# Adafruit_Infrared_IR_Remote_Receiver.net
KiCad netlist of a schematic drawn in EAGLE
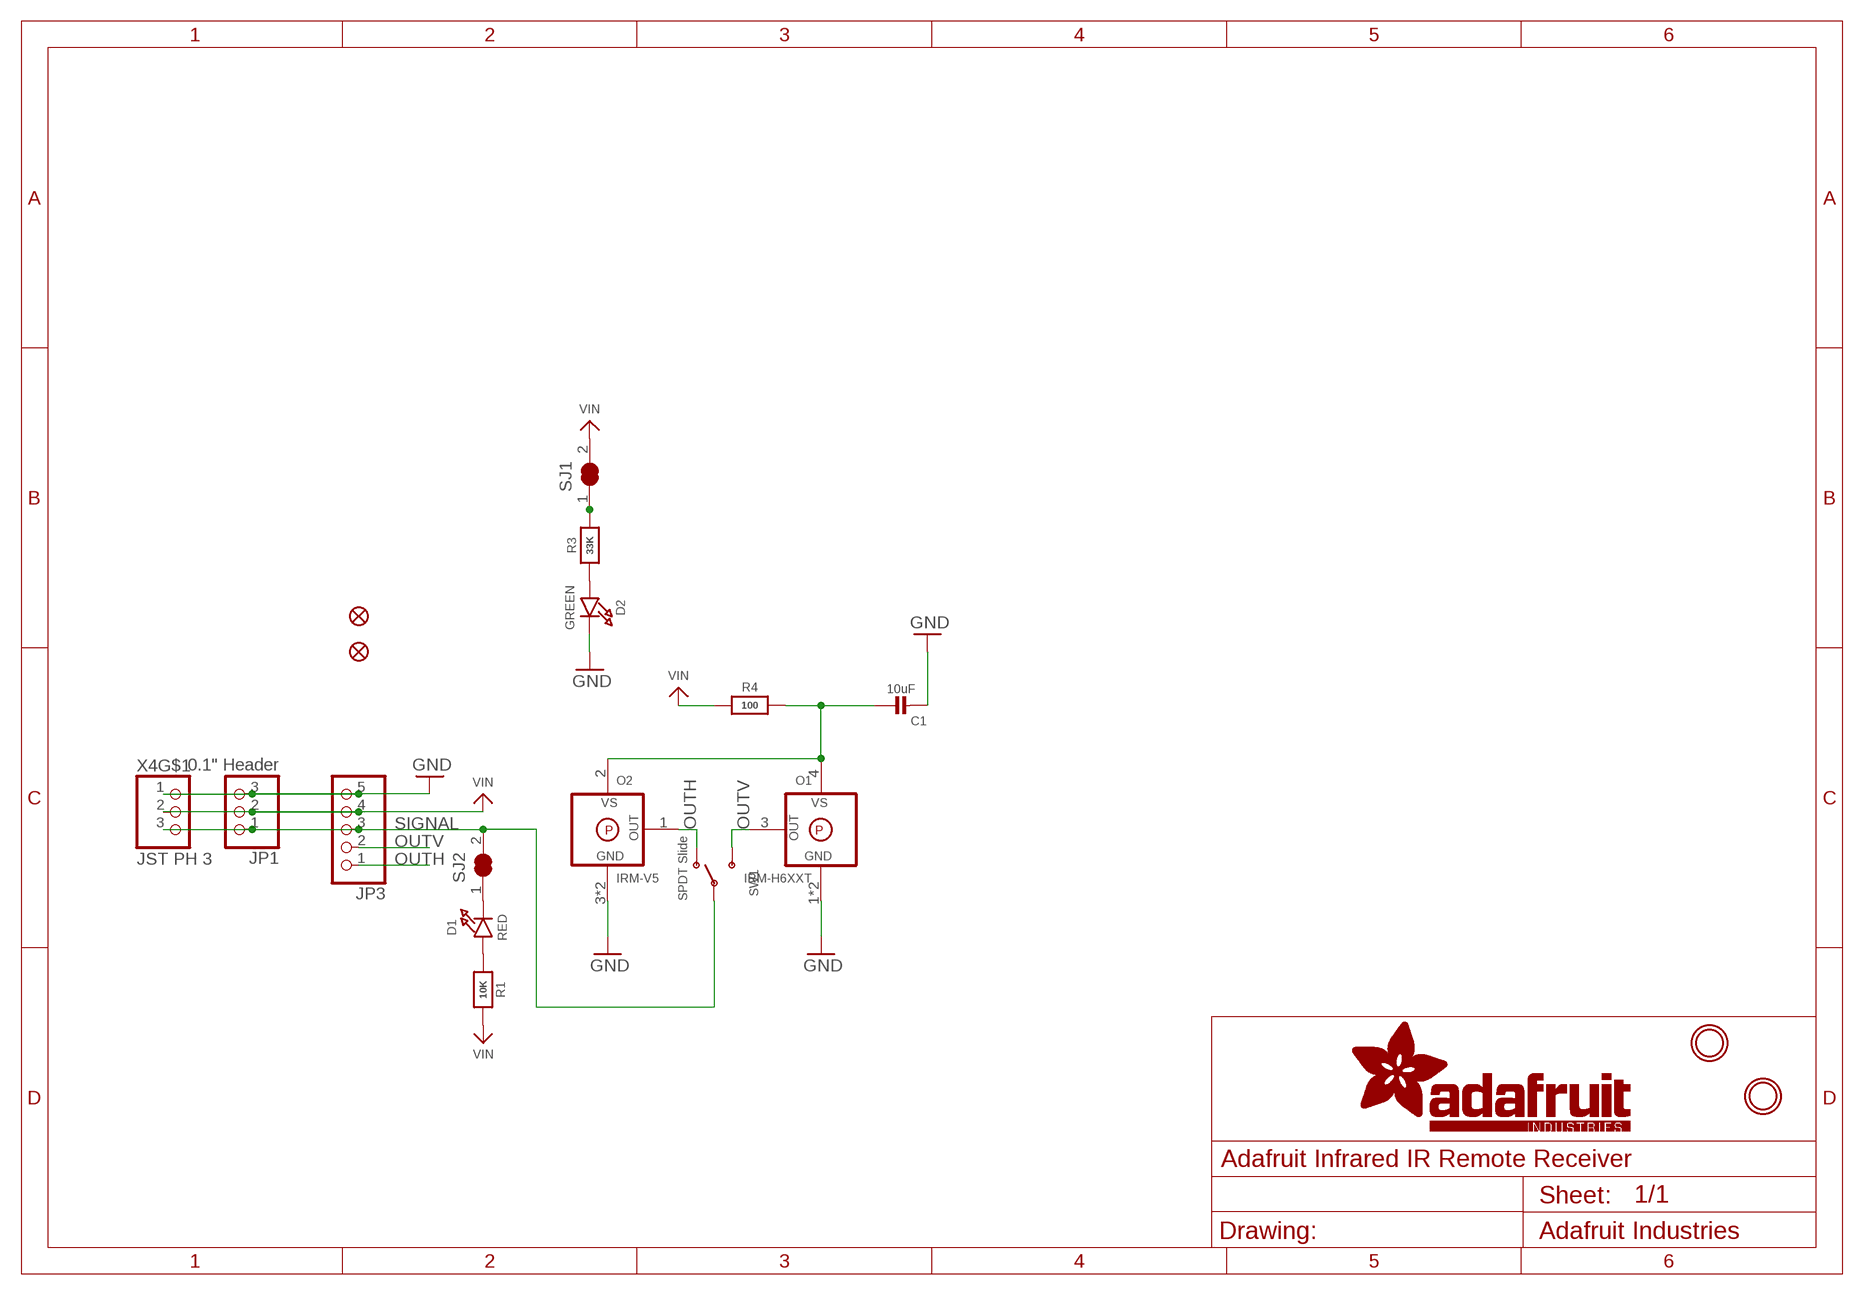
[diagram p0: schematic, sheet 1]

(export (version "E")
  (design (tool "Eeschema 10.0.6"))
  (components
    (comp (ref "C1")
      (value "10uF")
      (footprint "eagle-import:0805-NO")
      (libsource (lib "eagle-import") (part "CAP_CERAMIC0805-NOOUTLINE"))
    )
    (comp (ref "D1")
      (value "RED")
      (footprint "eagle-import:CHIPLED_0603_NOOUTLINE")
      (libsource (lib "eagle-import") (part "LED0603_NOOUTLINE"))
    )
    (comp (ref "D2")
      (value "GREEN")
      (footprint "eagle-import:CHIPLED_0603_NOOUTLINE")
      (libsource (lib "eagle-import") (part "LED0603_NOOUTLINE"))
    )
    (comp (ref "FID2")
      (value "FIDUCIAL_1MM")
      (footprint "eagle-import:FIDUCIAL_1MM")
      (libsource (lib "eagle-import") (part "FIDUCIAL_1MM"))
    )
    (comp (ref "FID3")
      (value "FIDUCIAL_1MM")
      (footprint "eagle-import:FIDUCIAL_1MM")
      (libsource (lib "eagle-import") (part "FIDUCIAL_1MM"))
    )
    (comp (ref "JP1")
      (value "0.1\" Header")
      (footprint "eagle-import:1X03_OVAL")
      (libsource (lib "eagle-import") (part "HEADER-1X3"))
    )
    (comp (ref "JP3")
      (value "HEADER-1X570MIL")
      (footprint "eagle-import:1X05_ROUND_70")
      (libsource (lib "eagle-import") (part "HEADER-1X570MIL"))
    )
    (comp (ref "O1")
      (value "IRM-H6XXT")
      (footprint "eagle-import:IRM-H6XXT")
      (libsource (lib "eagle-import") (part "GENERIC_IR_RECV_IRM-H6XXT"))
    )
    (comp (ref "O2")
      (value "IRM-V5")
      (footprint "eagle-import:IRM-V5")
      (libsource (lib "eagle-import") (part "GENERIC_IR_RECV_IRM-V5"))
    )
    (comp (ref "R1")
      (value "10K")
      (footprint "eagle-import:0603-NO")
      (libsource (lib "eagle-import") (part "RESISTOR_0603_NOOUT"))
    )
    (comp (ref "R3")
      (value "33K")
      (footprint "eagle-import:0603-NO")
      (libsource (lib "eagle-import") (part "RESISTOR_0603_NOOUT"))
    )
    (comp (ref "R4")
      (value "100")
      (footprint "eagle-import:0603-NO")
      (libsource (lib "eagle-import") (part "RESISTOR_0603_NOOUT"))
    )
    (comp (ref "SJ1")
      (value "SOLDERJUMPER_CLOSED")
      (footprint "eagle-import:SOLDERJUMPER_CLOSEDWIRE")
      (libsource (lib "eagle-import") (part "SOLDERJUMPER_CLOSED"))
    )
    (comp (ref "SJ2")
      (value "SOLDERJUMPER_CLOSED")
      (footprint "eagle-import:SOLDERJUMPER_CLOSEDWIRE")
      (libsource (lib "eagle-import") (part "SOLDERJUMPER_CLOSED"))
    )
    (comp (ref "SW1")
      (value "SPDT Slide")
      (footprint "eagle-import:SPDT_SMT_SSSS811101")
      (libsource (lib "eagle-import") (part "SWITCH_SPDT"))
    )
    (comp (ref "U$1")
      (value "MOUNTINGHOLE2.5")
      (footprint "eagle-import:MOUNTINGHOLE_2.5_PLATED")
      (libsource (lib "eagle-import") (part "MOUNTINGHOLE2.5"))
    )
    (comp (ref "U$8")
      (value "MOUNTINGHOLE2.5")
      (footprint "eagle-import:MOUNTINGHOLE_2.5_PLATED")
      (libsource (lib "eagle-import") (part "MOUNTINGHOLE2.5"))
    )
    (comp (ref "X4")
      (value "JST PH 3")
      (footprint "eagle-import:JSTPH3")
      (libsource (lib "eagle-import") (part "CON_JST_PH_3PIN"))
    )
  )
  (nets
    (net (code "1") (name "/OUTH") (class "Default")
      (node (ref "JP3") (pin "1") (pinfunction "1_1") (pintype "passive"))
      (node (ref "O2") (pin "1") (pinfunction "OUT_1") (pintype "output"))
      (node (ref "SW1") (pin "A") (pinfunction "O_A") (pintype "passive"))
    )
    (net (code "2") (name "/OUTV") (class "Default")
      (node (ref "JP3") (pin "2") (pinfunction "2_2") (pintype "passive"))
      (node (ref "O1") (pin "3") (pinfunction "OUT_3") (pintype "output"))
      (node (ref "SW1") (pin "C") (pinfunction "S_C") (pintype "passive"))
    )
    (net (code "3") (name "/SIGNAL") (class "Default")
      (node (ref "JP1") (pin "1") (pinfunction "1_1") (pintype "passive"))
      (node (ref "JP3") (pin "3") (pinfunction "3_3") (pintype "passive"))
      (node (ref "SJ2") (pin "2") (pinfunction "2_2") (pintype "passive"))
      (node (ref "SW1") (pin "B") (pinfunction "P_B") (pintype "passive"))
      (node (ref "X4") (pin "3") (pinfunction "3_3") (pintype "passive"))
    )
    (net (code "4") (name "GND") (class "Default")
      (node (ref "C1") (pin "2") (pinfunction "2_2") (pintype "passive"))
      (node (ref "D2") (pin "C") (pinfunction "C_C") (pintype "passive"))
      (node (ref "JP1") (pin "3") (pinfunction "3_3") (pintype "passive"))
      (node (ref "JP3") (pin "5") (pinfunction "5_5") (pintype "passive"))
      (node (ref "O1") (pin "1") (pinfunction "GND_1") (pintype "power_in"))
      (node (ref "O1") (pin "2") (pinfunction "GND_2") (pintype "power_in"))
      (node (ref "O2") (pin "3") (pinfunction "GND_3") (pintype "power_in"))
      (node (ref "O2") (pin "MT") (pinfunction "GND_MT") (pintype "power_in"))
      (node (ref "X4") (pin "1") (pinfunction "1_1") (pintype "passive"))
    )
    (net (code "5") (name "Net-(D1-PadA)") (class "Default")
      (node (ref "D1") (pin "A") (pinfunction "A_A") (pintype "passive"))
      (node (ref "R1") (pin "1") (pinfunction "1_1") (pintype "passive"))
    )
    (net (code "6") (name "Net-(D1-PadC)") (class "Default")
      (node (ref "D1") (pin "C") (pinfunction "C_C") (pintype "passive"))
      (node (ref "SJ2") (pin "1") (pinfunction "1_1") (pintype "passive"))
    )
    (net (code "7") (name "Net-(D2-PadA)") (class "Default")
      (node (ref "D2") (pin "A") (pinfunction "A_A") (pintype "passive"))
      (node (ref "R3") (pin "1") (pinfunction "1_1") (pintype "passive"))
    )
    (net (code "8") (name "Net-(O1-VS)") (class "Default")
      (node (ref "C1") (pin "1") (pinfunction "1_1") (pintype "passive"))
      (node (ref "O1") (pin "4") (pinfunction "VS_4") (pintype "power_in"))
      (node (ref "O2") (pin "2") (pinfunction "VS_2") (pintype "power_in"))
      (node (ref "R4") (pin "2") (pinfunction "2_2") (pintype "passive"))
    )
    (net (code "9") (name "Net-(R3-Pad2)") (class "Default")
      (node (ref "R3") (pin "2") (pinfunction "2_2") (pintype "passive"))
      (node (ref "SJ1") (pin "1") (pinfunction "1_1") (pintype "passive"))
    )
    (net (code "10") (name "VIN") (class "Default")
      (node (ref "JP1") (pin "2") (pinfunction "2_2") (pintype "passive"))
      (node (ref "JP3") (pin "4") (pinfunction "4_4") (pintype "passive"))
      (node (ref "R1") (pin "2") (pinfunction "2_2") (pintype "passive"))
      (node (ref "R4") (pin "1") (pinfunction "1_1") (pintype "passive"))
      (node (ref "SJ1") (pin "2") (pinfunction "2_2") (pintype "passive"))
      (node (ref "X4") (pin "2") (pinfunction "2_2") (pintype "passive"))
    )
  )
)
